# LowVoltageShutdown.net
KiCad netlist of a schematic drawn in EAGLE
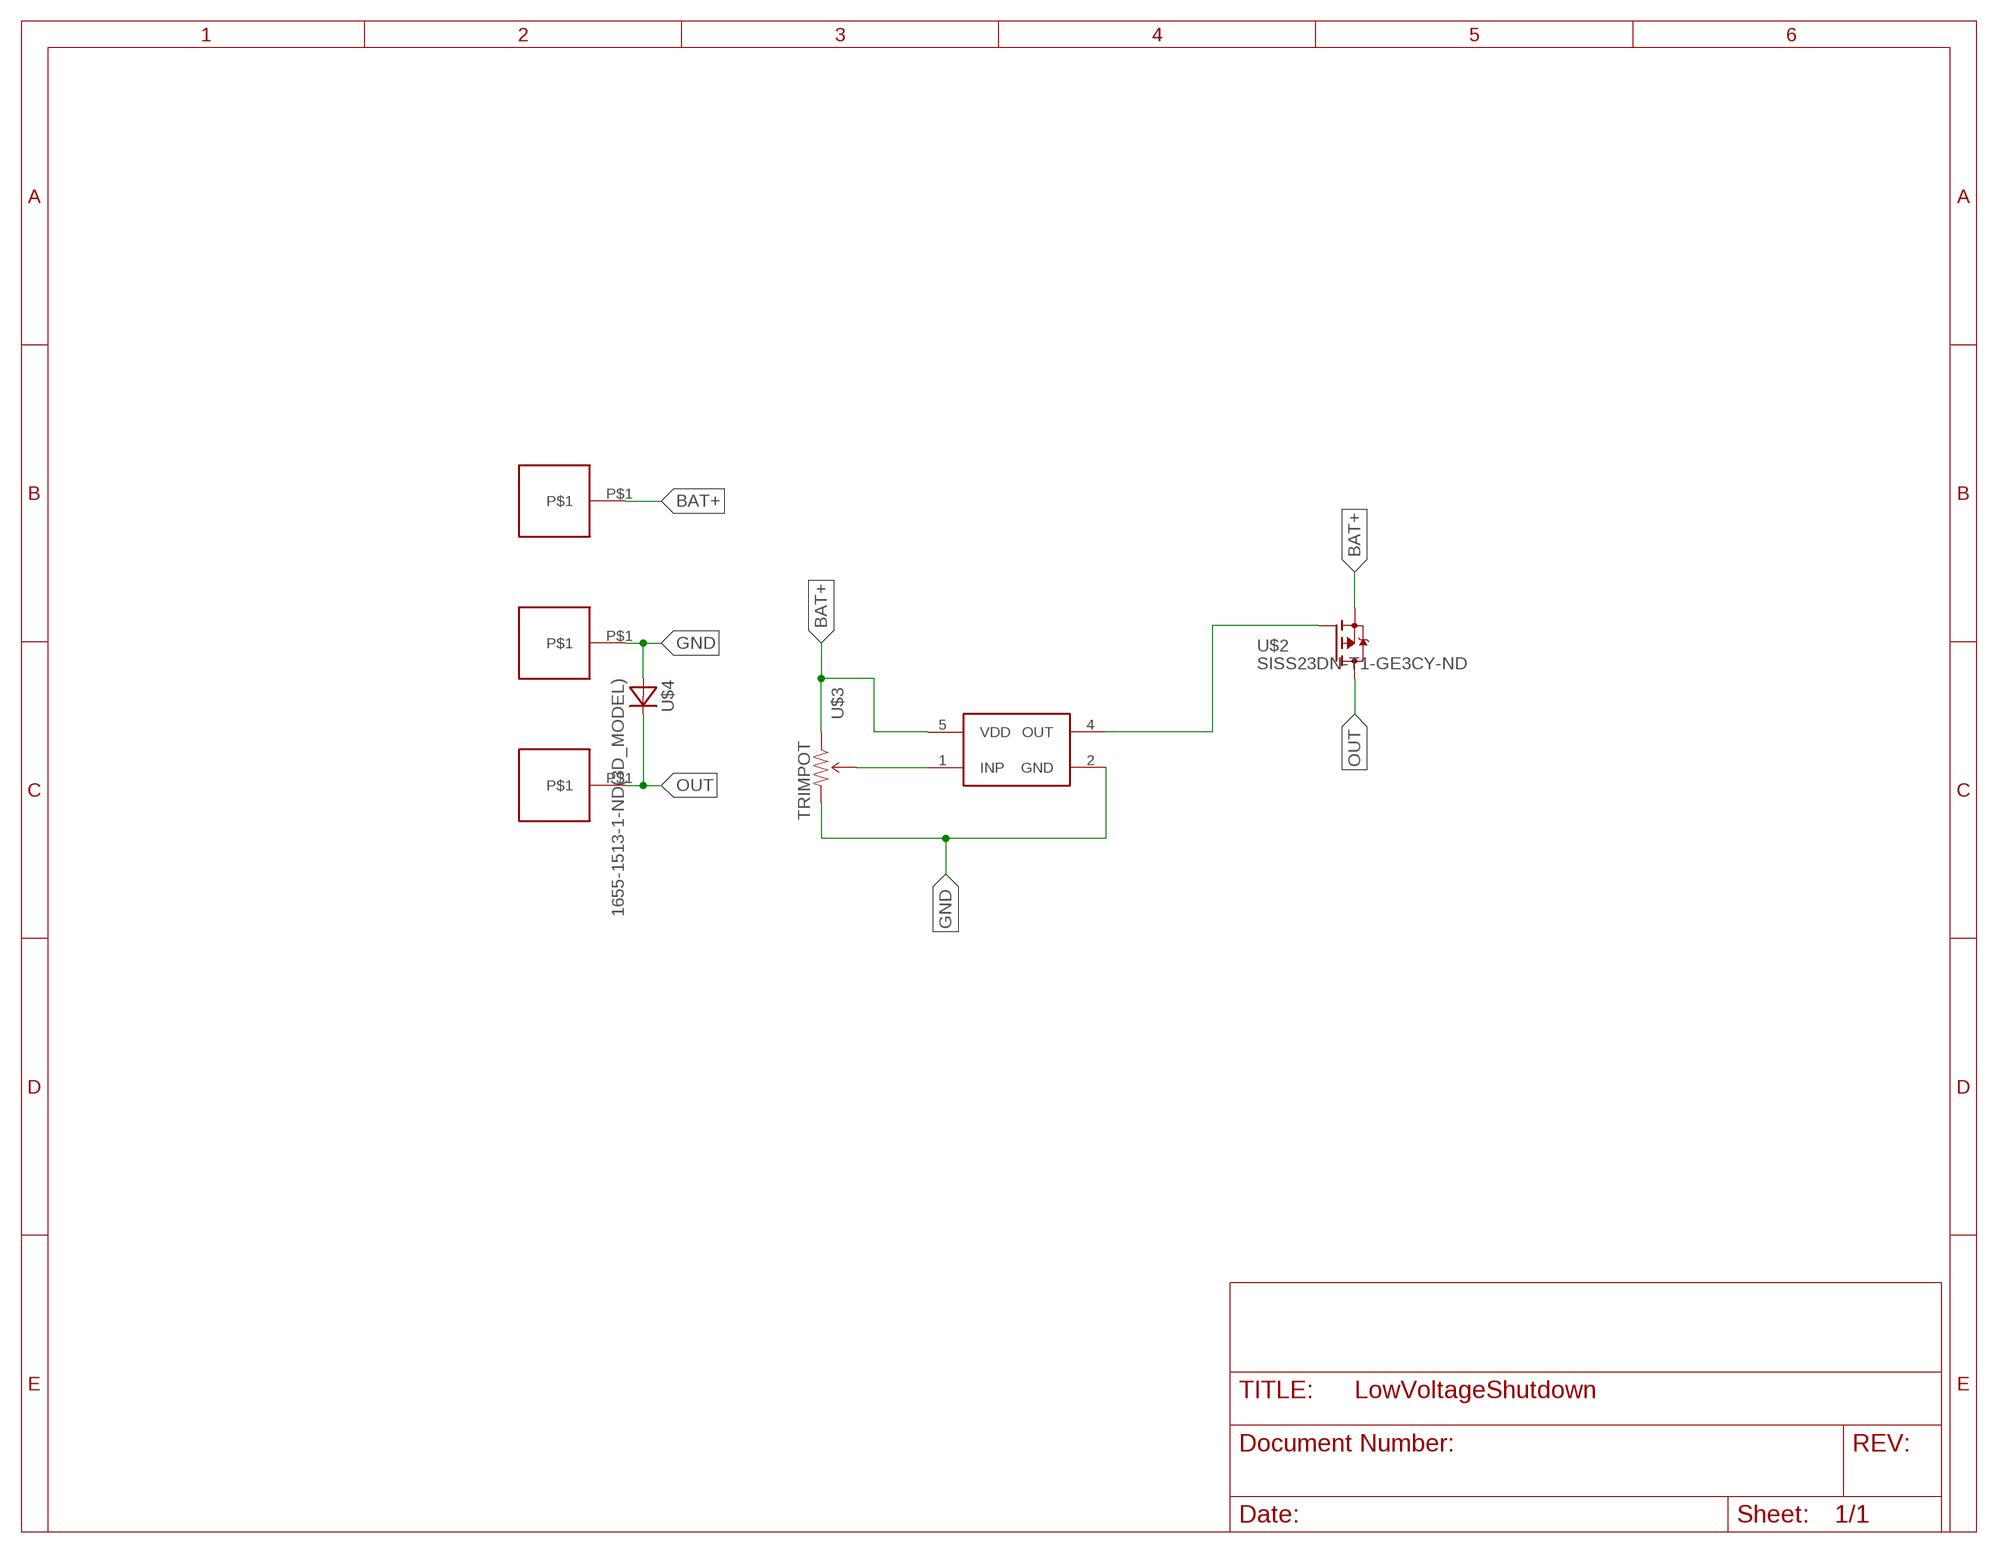
[diagram p0: schematic, sheet 1]

(export (version "E")
  (design (tool "Eeschema 10.0.6"))
  (components
    (comp (ref "BAT+")
      (value "16G")
      (footprint "eagle-import:16G")
      (libsource (lib "eagle-import") (part "16G"))
    )
    (comp (ref "GND")
      (value "16G")
      (footprint "eagle-import:16G")
      (libsource (lib "eagle-import") (part "16G"))
    )
    (comp (ref "OUT")
      (value "16G")
      (footprint "eagle-import:16G")
      (libsource (lib "eagle-import") (part "16G"))
    )
    (comp (ref "U$1")
      (value "MIC842L(3D_MODEL)")
      (footprint "eagle-import:SOTFL65P210X110-5")
      (libsource (lib "eagle-import") (part "MIC842L(3D_MODEL)"))
    )
    (comp (ref "U$2")
      (value "SISS23DN-T1-GE3CY-ND")
      (footprint "eagle-import:POWERPAK1212-8S")
      (libsource (lib "eagle-import") (part "SISS23DN-T1-GE3CY-ND"))
    )
    (comp (ref "U$3")
      (value "TRIMPOT")
      (footprint "eagle-import:490-2877-ND")
      (libsource (lib "eagle-import") (part "TRIMPOT"))
    )
    (comp (ref "U$4")
      (value "1655-1513-1-ND(3D_MODEL)")
      (footprint "eagle-import:DIOAD1950W130L900D530B")
      (libsource (lib "eagle-import") (part "1655-1513-1-ND(3D_MODEL)"))
    )
  )
  (nets
    (net (code "1") (name "BAT+") (class "Default")
      (node (ref "BAT+") (pin "P$1") (pinfunction "P$1_P$1") (pintype "bidirectional"))
      (node (ref "U$1") (pin "5") (pinfunction "VDD_5") (pintype "bidirectional"))
      (node (ref "U$2") (pin "S") (pinfunction "S_S") (pintype "passive"))
      (node (ref "U$3") (pin "P$1") (pinfunction "CCW_P$1") (pintype "passive"))
    )
    (net (code "2") (name "GND") (class "Default")
      (node (ref "GND") (pin "P$1") (pinfunction "P$1_P$1") (pintype "bidirectional"))
      (node (ref "U$1") (pin "2") (pinfunction "GND_2") (pintype "bidirectional"))
      (node (ref "U$3") (pin "P$3") (pinfunction "CW_P$3") (pintype "passive"))
      (node (ref "U$4") (pin "2") (pinfunction "A_2") (pintype "passive"))
    )
    (net (code "3") (name "Net-(U$1-INP)") (class "Default")
      (node (ref "U$1") (pin "1") (pinfunction "INP_1") (pintype "bidirectional"))
      (node (ref "U$3") (pin "P$2") (pinfunction "WIPER_P$2") (pintype "passive"))
    )
    (net (code "4") (name "Net-(U$1-OUT)") (class "Default")
      (node (ref "U$1") (pin "4") (pinfunction "OUT_4") (pintype "bidirectional"))
      (node (ref "U$2") (pin "G") (pinfunction "G_G") (pintype "passive"))
    )
    (net (code "5") (name "OUT") (class "Default")
      (node (ref "OUT") (pin "P$1") (pinfunction "P$1_P$1") (pintype "bidirectional"))
      (node (ref "U$2") (pin "D") (pinfunction "D_D") (pintype "passive"))
      (node (ref "U$4") (pin "1") (pinfunction "C_1") (pintype "passive"))
    )
  )
)
